# VGAX_board_rev_11_PAPER_VERSION_option_2.net
KiCad netlist of a schematic drawn in EAGLE
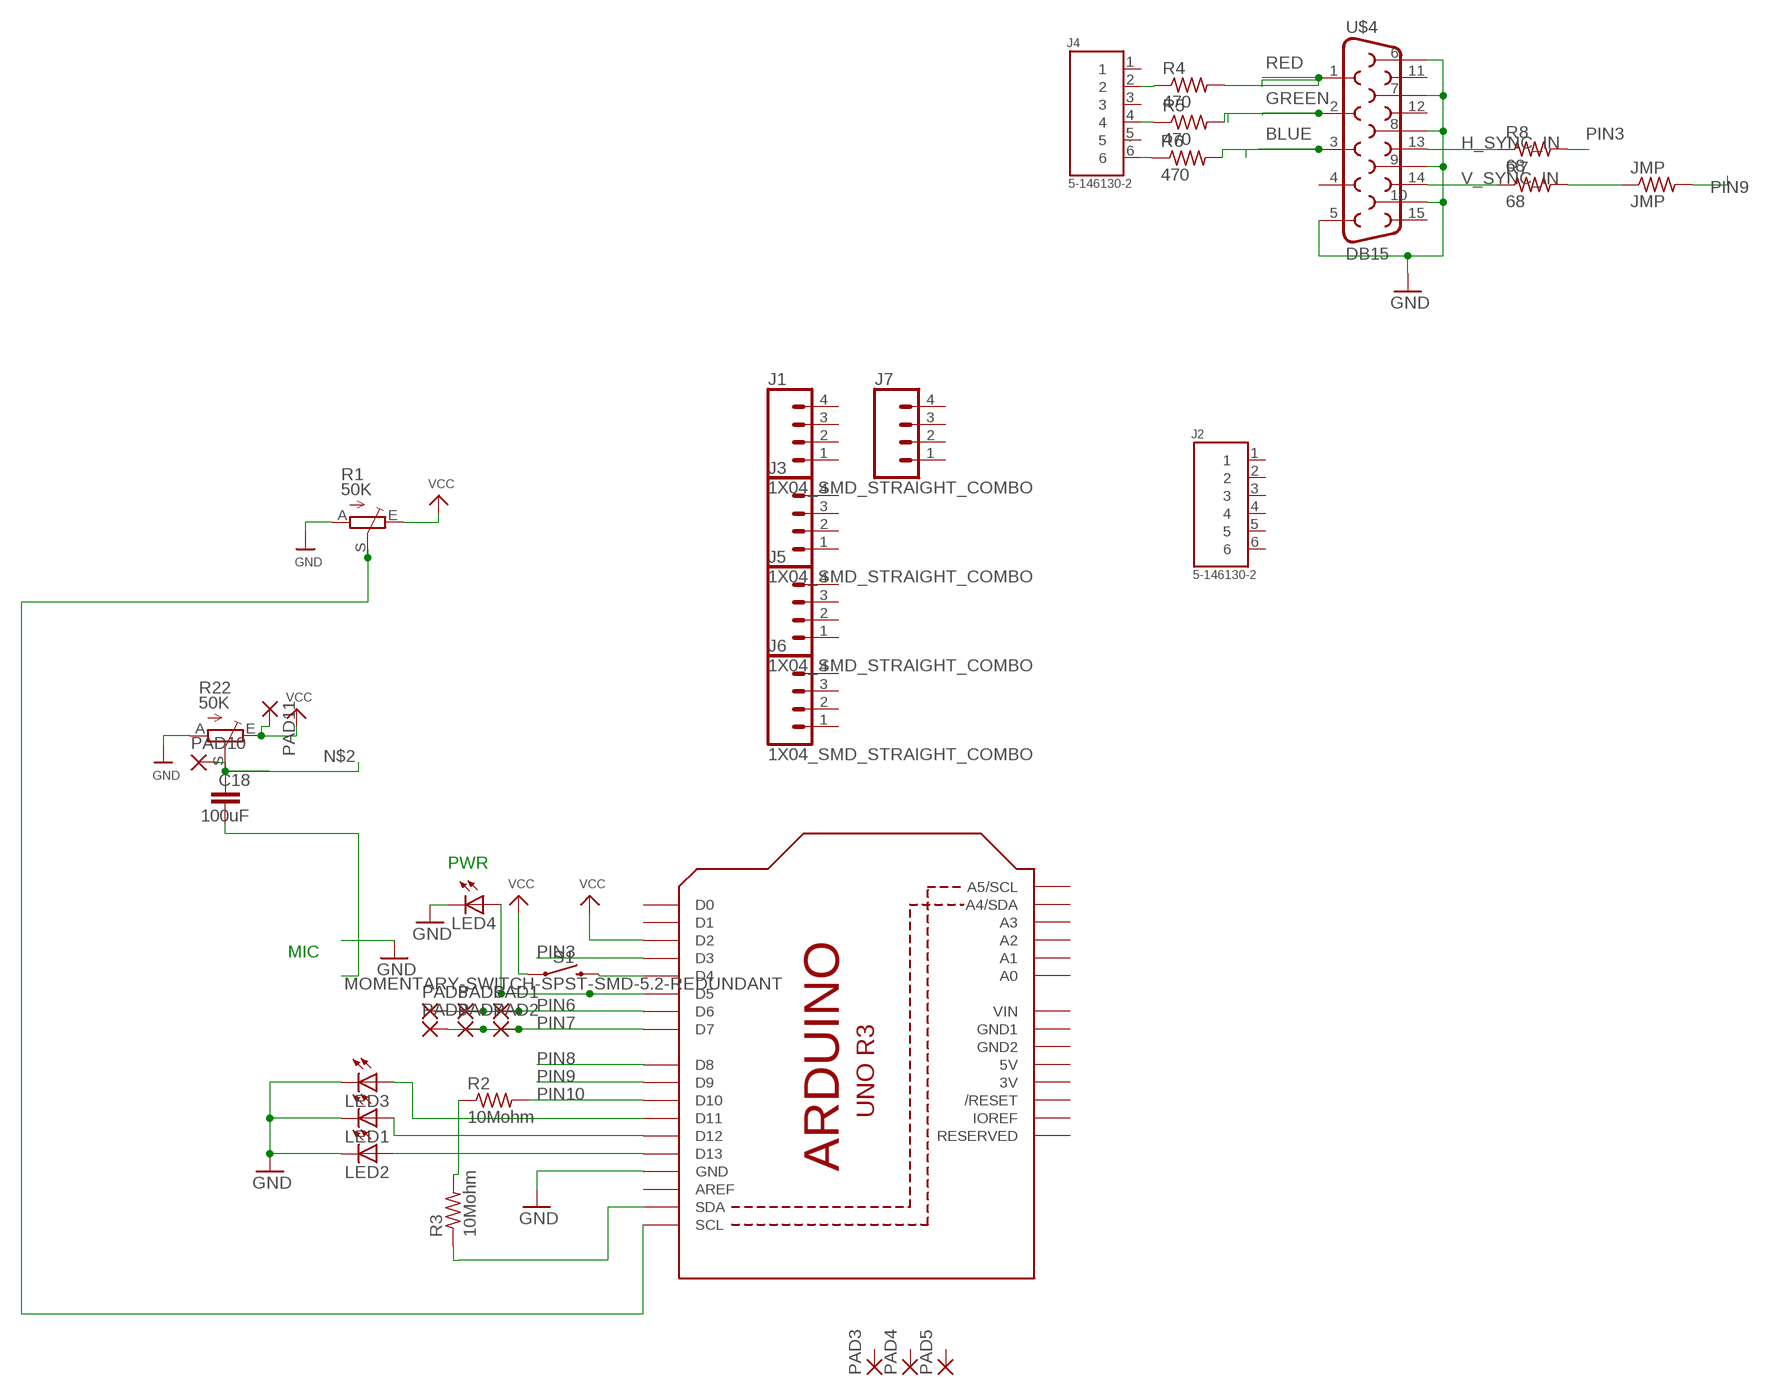
[diagram p0: schematic, sheet 1]

(export (version "E")
  (design (tool "Eeschema 10.0.6"))
  (components
    (comp (ref "C18")
      (value "100uF")
      (footprint "eagle-import:1206")
      (libsource (lib "eagle-import") (part "1.0UF-1206-50V-10%"))
    )
    (comp (ref "J1")
      (value "1X04_SMD_STRAIGHT_COMBO")
      (footprint "eagle-import:1X04_SMD_VERTICAL_COMBO")
      (libsource (lib "eagle-import") (part "CONN_04SMD_STRAIGHT_COMBO"))
    )
    (comp (ref "J2")
      (value "5-146130-2")
      (footprint "eagle-import:5-146130-2")
      (fields
        (field (name "DIGIKEY_PART_NUMBER") "5-146130-2-ND")
        (field (name "MANUFACTURER") "TE Connectivity AMP Connectors")
        (field (name "CREATED_BY") "PCBLayout.com")
      )
      (libsource (lib "eagle-import") (part "5-146130-2"))
    )
    (comp (ref "J3")
      (value "1X04_SMD_STRAIGHT_COMBO")
      (footprint "eagle-import:1X04_SMD_VERTICAL_COMBO")
      (libsource (lib "eagle-import") (part "CONN_04SMD_STRAIGHT_COMBO"))
    )
    (comp (ref "J4")
      (value "5-146130-2")
      (footprint "eagle-import:5-146130-2")
      (fields
        (field (name "DIGIKEY_PART_NUMBER") "5-146130-2-ND")
        (field (name "MANUFACTURER") "TE Connectivity AMP Connectors")
        (field (name "CREATED_BY") "PCBLayout.com")
      )
      (libsource (lib "eagle-import") (part "5-146130-2"))
    )
    (comp (ref "J5")
      (value "1X04_SMD_STRAIGHT_COMBO")
      (footprint "eagle-import:1X04_SMD_VERTICAL_COMBO")
      (libsource (lib "eagle-import") (part "CONN_04SMD_STRAIGHT_COMBO"))
    )
    (comp (ref "J6")
      (value "1X04_SMD_STRAIGHT_COMBO")
      (footprint "eagle-import:1X04_SMD_VERTICAL_COMBO")
      (libsource (lib "eagle-import") (part "CONN_04SMD_STRAIGHT_COMBO"))
    )
    (comp (ref "J7")
      (value "1X04_SMD_STRAIGHT_COMBO")
      (footprint "eagle-import:1X04_SMD_VERTICAL_COMBO")
      (libsource (lib "eagle-import") (part "CONN_04SMD_STRAIGHT_COMBO"))
    )
    (comp (ref "JMP")
      (value "JMP")
      (footprint "eagle-import:M1206")
      (libsource (lib "eagle-import") (part "R-US_M1206"))
    )
    (comp (ref "LED1")
      (value "LEDCHIPLED_1206")
      (footprint "eagle-import:CHIPLED_1206")
      (libsource (lib "eagle-import") (part "LEDCHIPLED_1206"))
    )
    (comp (ref "LED2")
      (value "LEDCHIPLED_1206")
      (footprint "eagle-import:CHIPLED_1206")
      (libsource (lib "eagle-import") (part "LEDCHIPLED_1206"))
    )
    (comp (ref "LED3")
      (value "LEDCHIPLED_1206")
      (footprint "eagle-import:CHIPLED_1206")
      (libsource (lib "eagle-import") (part "LEDCHIPLED_1206"))
    )
    (comp (ref "LED4")
      (value "LEDCHIPLED_1206")
      (footprint "eagle-import:CHIPLED_1206")
      (libsource (lib "eagle-import") (part "LEDCHIPLED_1206"))
    )
    (comp (ref "PAD1")
      (value "SMD2")
      (footprint "eagle-import:SMD1,27-2,54")
      (libsource (lib "eagle-import") (part "SMD2"))
    )
    (comp (ref "PAD2")
      (value "SMD2")
      (footprint "eagle-import:SMD1,27-2,54")
      (libsource (lib "eagle-import") (part "SMD2"))
    )
    (comp (ref "PAD3")
      (value "SMD2")
      (footprint "eagle-import:SMD1,27-2,54")
      (libsource (lib "eagle-import") (part "SMD2"))
    )
    (comp (ref "PAD4")
      (value "SMD2")
      (footprint "eagle-import:SMD1,27-2,54")
      (libsource (lib "eagle-import") (part "SMD2"))
    )
    (comp (ref "PAD5")
      (value "SMD2")
      (footprint "eagle-import:SMD1,27-2,54")
      (libsource (lib "eagle-import") (part "SMD2"))
    )
    (comp (ref "PAD6")
      (value "SMD2")
      (footprint "eagle-import:SMD1,27-2,54")
      (libsource (lib "eagle-import") (part "SMD2"))
    )
    (comp (ref "PAD7")
      (value "SMD2")
      (footprint "eagle-import:SMD1,27-2,54")
      (libsource (lib "eagle-import") (part "SMD2"))
    )
    (comp (ref "PAD8")
      (value "SMD2")
      (footprint "eagle-import:SMD1,27-2,54")
      (libsource (lib "eagle-import") (part "SMD2"))
    )
    (comp (ref "PAD9")
      (value "SMD2")
      (footprint "eagle-import:SMD1,27-2,54")
      (libsource (lib "eagle-import") (part "SMD2"))
    )
    (comp (ref "PAD10")
      (value "SMD2")
      (footprint "eagle-import:SMD1,27-2,54")
      (libsource (lib "eagle-import") (part "SMD2"))
    )
    (comp (ref "PAD11")
      (value "SMD2")
      (footprint "eagle-import:SMD1,27-2,54")
      (libsource (lib "eagle-import") (part "SMD2"))
    )
    (comp (ref "R1")
      (value "50K")
      (footprint "eagle-import:CA9V")
      (libsource (lib "eagle-import") (part "TRIM_EU-CA9V"))
    )
    (comp (ref "R2")
      (value "10Mohm")
      (footprint "eagle-import:M1206")
      (libsource (lib "eagle-import") (part "R-US_M1206"))
    )
    (comp (ref "R3")
      (value "10Mohm")
      (footprint "eagle-import:M1206")
      (libsource (lib "eagle-import") (part "R-US_M1206"))
    )
    (comp (ref "R4")
      (value "470")
      (footprint "eagle-import:M1206")
      (libsource (lib "eagle-import") (part "R-US_M1206"))
    )
    (comp (ref "R5")
      (value "470")
      (footprint "eagle-import:M1206")
      (libsource (lib "eagle-import") (part "R-US_M1206"))
    )
    (comp (ref "R6")
      (value "470")
      (footprint "eagle-import:M1206")
      (libsource (lib "eagle-import") (part "R-US_M1206"))
    )
    (comp (ref "R7")
      (value "68")
      (footprint "eagle-import:M1206")
      (libsource (lib "eagle-import") (part "R-US_M1206"))
    )
    (comp (ref "R8")
      (value "68")
      (footprint "eagle-import:M1206")
      (libsource (lib "eagle-import") (part "R-US_M1206"))
    )
    (comp (ref "R22")
      (value "50K")
      (footprint "eagle-import:CA9V")
      (libsource (lib "eagle-import") (part "TRIM_EU-CA9V"))
    )
    (comp (ref "S1")
      (value "MOMENTARY-SWITCH-SPST-SMD-5.2-REDUNDANT")
      (footprint "eagle-import:TACTILE_SWITCH_SMD_5.2MM")
      (libsource (lib "eagle-import") (part "MOMENTARY-SWITCH-SPST-SMD-5.2-REDUNDANT"))
    )
    (comp (ref "U$4")
      (value "DB15")
      (footprint "eagle-import:DB15")
      (libsource (lib "eagle-import") (part "DB15"))
    )
    (comp (ref "U1")
      (value "ARDUINOR3-BPLACE")
      (footprint "eagle-import:ARDUINOR3-BPLACE")
      (libsource (lib "eagle-import") (part "ARDUINOR3-BPLACE"))
    )
  )
  (nets
    (net (code "1") (name "/3V") (class "Default")
      (node (ref "U1") (pin "3V") (pinfunction "3V_3V") (pintype "power_in"))
    )
    (net (code "2") (name "/5V") (class "Default")
      (node (ref "U1") (pin "5V") (pinfunction "5V_5V") (pintype "power_in"))
    )
    (net (code "3") (name "/BLUE") (class "Default")
      (node (ref "R6") (pin "2") (pinfunction "2_2") (pintype "passive"))
      (node (ref "U$4") (pin "3") (pinfunction "3_3") (pintype "passive"))
    )
    (net (code "4") (name "/GND1") (class "Default")
      (node (ref "U1") (pin "GND1") (pinfunction "GND1_GND1") (pintype "power_in"))
    )
    (net (code "5") (name "/GND2") (class "Default")
      (node (ref "U1") (pin "GND2") (pinfunction "GND2_GND2") (pintype "power_in"))
    )
    (net (code "6") (name "/GREEN") (class "Default")
      (node (ref "R5") (pin "2") (pinfunction "2_2") (pintype "passive"))
      (node (ref "U$4") (pin "2") (pinfunction "2_2") (pintype "passive"))
    )
    (net (code "7") (name "/H_SYNC_IN") (class "Default")
      (node (ref "R8") (pin "1") (pinfunction "1_1") (pintype "passive"))
      (node (ref "U$4") (pin "13") (pinfunction "13_13") (pintype "passive"))
    )
    (net (code "8") (name "/N$2") (class "Default")
      (node (ref "C18") (pin "1") (pinfunction "1_1") (pintype "passive"))
      (node (ref "PAD10") (pin "1") (pinfunction "P_1") (pintype "passive"))
      (node (ref "R22") (pin "S") (pinfunction "S_S") (pintype "passive"))
    )
    (net (code "9") (name "/PIN3") (class "Default")
      (node (ref "R8") (pin "2") (pinfunction "2_2") (pintype "passive"))
      (node (ref "U1") (pin "D3") (pinfunction "D3_D3") (pintype "bidirectional"))
    )
    (net (code "10") (name "/PIN6") (class "Default")
      (node (ref "PAD1") (pin "1") (pinfunction "P_1") (pintype "passive"))
      (node (ref "PAD6") (pin "1") (pinfunction "P_1") (pintype "passive"))
      (node (ref "PAD8") (pin "1") (pinfunction "P_1") (pintype "passive"))
      (node (ref "U1") (pin "D6") (pinfunction "D6_D6") (pintype "bidirectional"))
    )
    (net (code "11") (name "/PIN7") (class "Default")
      (node (ref "PAD2") (pin "1") (pinfunction "P_1") (pintype "passive"))
      (node (ref "PAD7") (pin "1") (pinfunction "P_1") (pintype "passive"))
      (node (ref "PAD9") (pin "1") (pinfunction "P_1") (pintype "passive"))
      (node (ref "U1") (pin "D7") (pinfunction "D7_D7") (pintype "bidirectional"))
    )
    (net (code "12") (name "/PIN8") (class "Default")
      (node (ref "R3") (pin "1") (pinfunction "1_1") (pintype "passive"))
      (node (ref "U1") (pin "D8") (pinfunction "D8_D8") (pintype "bidirectional"))
      (node (ref "U1") (pin "SDA") (pinfunction "SDA_SDA") (pintype "bidirectional"))
    )
    (net (code "13") (name "/PIN9") (class "Default")
      (node (ref "JMP") (pin "2") (pinfunction "2_2") (pintype "passive"))
      (node (ref "U1") (pin "D9") (pinfunction "D9_D9") (pintype "bidirectional"))
    )
    (net (code "14") (name "/PIN10") (class "Default")
      (node (ref "R2") (pin "2") (pinfunction "2_2") (pintype "passive"))
      (node (ref "U1") (pin "D10") (pinfunction "D10_D10") (pintype "bidirectional"))
    )
    (net (code "15") (name "/RED") (class "Default")
      (node (ref "R4") (pin "2") (pinfunction "2_2") (pintype "passive"))
      (node (ref "U$4") (pin "1") (pinfunction "1_1") (pintype "passive"))
    )
    (net (code "16") (name "/VIN") (class "Default")
      (node (ref "U1") (pin "VIN") (pinfunction "VIN_VIN") (pintype "power_in"))
    )
    (net (code "17") (name "/V_SYNC_IN") (class "Default")
      (node (ref "R7") (pin "1") (pinfunction "1_1") (pintype "passive"))
      (node (ref "U$4") (pin "14") (pinfunction "14_14") (pintype "passive"))
    )
    (net (code "18") (name "GND") (class "Default")
      (node (ref "LED1") (pin "C") (pinfunction "C_C") (pintype "passive"))
      (node (ref "LED2") (pin "C") (pinfunction "C_C") (pintype "passive"))
      (node (ref "LED3") (pin "C") (pinfunction "C_C") (pintype "passive"))
      (node (ref "LED4") (pin "C") (pinfunction "C_C") (pintype "passive"))
      (node (ref "R1") (pin "A") (pinfunction "A_A") (pintype "passive"))
      (node (ref "R22") (pin "A") (pinfunction "A_A") (pintype "passive"))
      (node (ref "U$4") (pin "10") (pinfunction "10_10") (pintype "passive"))
      (node (ref "U$4") (pin "5") (pinfunction "5_5") (pintype "passive"))
      (node (ref "U$4") (pin "6") (pinfunction "6_6") (pintype "passive"))
      (node (ref "U$4") (pin "7") (pinfunction "7_7") (pintype "passive"))
      (node (ref "U$4") (pin "8") (pinfunction "8_8") (pintype "passive"))
      (node (ref "U$4") (pin "9") (pinfunction "9_9") (pintype "passive"))
      (node (ref "U1") (pin "GND") (pinfunction "GND_GND") (pintype "power_in"))
    )
    (net (code "19") (name "Net-(J4-Pad2)") (class "Default")
      (node (ref "J4") (pin "2") (pinfunction "2_2") (pintype "passive"))
      (node (ref "R4") (pin "1") (pinfunction "1_1") (pintype "passive"))
    )
    (net (code "20") (name "Net-(J4-Pad4)") (class "Default")
      (node (ref "J4") (pin "4") (pinfunction "4_4") (pintype "passive"))
      (node (ref "R5") (pin "1") (pinfunction "1_1") (pintype "passive"))
    )
    (net (code "21") (name "Net-(J4-Pad6)") (class "Default")
      (node (ref "J4") (pin "6") (pinfunction "6_6") (pintype "passive"))
      (node (ref "R6") (pin "1") (pinfunction "1_1") (pintype "passive"))
    )
    (net (code "22") (name "Net-(JMP-Pad1)") (class "Default")
      (node (ref "JMP") (pin "1") (pinfunction "1_1") (pintype "passive"))
      (node (ref "R7") (pin "2") (pinfunction "2_2") (pintype "passive"))
    )
    (net (code "23") (name "Net-(LED1-PadA)") (class "Default")
      (node (ref "LED1") (pin "A") (pinfunction "A_A") (pintype "passive"))
      (node (ref "U1") (pin "D12") (pinfunction "D12_D12") (pintype "bidirectional"))
    )
    (net (code "24") (name "Net-(LED2-PadA)") (class "Default")
      (node (ref "LED2") (pin "A") (pinfunction "A_A") (pintype "passive"))
      (node (ref "U1") (pin "D13") (pinfunction "D13_D13") (pintype "bidirectional"))
    )
    (net (code "25") (name "Net-(LED3-PadA)") (class "Default")
      (node (ref "LED3") (pin "A") (pinfunction "A_A") (pintype "passive"))
      (node (ref "U1") (pin "D11") (pinfunction "D11_D11") (pintype "bidirectional"))
    )
    (net (code "26") (name "Net-(LED4-PadA)") (class "Default")
      (node (ref "LED4") (pin "A") (pinfunction "A_A") (pintype "passive"))
      (node (ref "U1") (pin "D5") (pinfunction "D5_D5") (pintype "bidirectional"))
    )
    (net (code "27") (name "Net-(R1-PadS)") (class "Default")
      (node (ref "R1") (pin "S") (pinfunction "S_S") (pintype "passive"))
      (node (ref "U1") (pin "SCL") (pinfunction "SCL_SCL") (pintype "bidirectional"))
    )
    (net (code "28") (name "Net-(R2-Pad1)") (class "Default")
      (node (ref "R2") (pin "1") (pinfunction "1_1") (pintype "passive"))
      (node (ref "R3") (pin "2") (pinfunction "2_2") (pintype "passive"))
    )
    (net (code "29") (name "Net-(S1-2-Pad3)") (class "Default")
      (node (ref "S1") (pin "3") (pinfunction "2_3") (pintype "passive"))
      (node (ref "S1") (pin "4") (pinfunction "2_4") (pintype "passive"))
      (node (ref "U1") (pin "D4") (pinfunction "D4_D4") (pintype "bidirectional"))
    )
    (net (code "30") (name "VCC") (class "Default")
      (node (ref "PAD11") (pin "1") (pinfunction "P_1") (pintype "passive"))
      (node (ref "R1") (pin "E") (pinfunction "E_E") (pintype "passive"))
      (node (ref "R22") (pin "E") (pinfunction "E_E") (pintype "passive"))
      (node (ref "S1") (pin "1") (pinfunction "1_1") (pintype "passive"))
      (node (ref "S1") (pin "2") (pinfunction "1_2") (pintype "passive"))
      (node (ref "U1") (pin "D2") (pinfunction "D2_D2") (pintype "bidirectional"))
    )
    (net (code "31") (name "unconnected-(C18-Pad2)") (class "Default")
      (node (ref "C18") (pin "2") (pinfunction "2_2") (pintype "passive"))
    )
    (net (code "32") (name "unconnected-(J1-Pad1)") (class "Default")
      (node (ref "J1") (pin "1") (pinfunction "1_1") (pintype "passive"))
    )
    (net (code "33") (name "unconnected-(J1-Pad2)") (class "Default")
      (node (ref "J1") (pin "2") (pinfunction "2_2") (pintype "passive"))
    )
    (net (code "34") (name "unconnected-(J1-Pad3)") (class "Default")
      (node (ref "J1") (pin "3") (pinfunction "3_3") (pintype "passive"))
    )
    (net (code "35") (name "unconnected-(J1-Pad4)") (class "Default")
      (node (ref "J1") (pin "4") (pinfunction "4_4") (pintype "passive"))
    )
    (net (code "36") (name "unconnected-(J2-Pad1)") (class "Default")
      (node (ref "J2") (pin "1") (pinfunction "1_1") (pintype "passive"))
    )
    (net (code "37") (name "unconnected-(J2-Pad2)") (class "Default")
      (node (ref "J2") (pin "2") (pinfunction "2_2") (pintype "passive"))
    )
    (net (code "38") (name "unconnected-(J2-Pad3)") (class "Default")
      (node (ref "J2") (pin "3") (pinfunction "3_3") (pintype "passive"))
    )
    (net (code "39") (name "unconnected-(J2-Pad4)") (class "Default")
      (node (ref "J2") (pin "4") (pinfunction "4_4") (pintype "passive"))
    )
    (net (code "40") (name "unconnected-(J2-Pad5)") (class "Default")
      (node (ref "J2") (pin "5") (pinfunction "5_5") (pintype "passive"))
    )
    (net (code "41") (name "unconnected-(J2-Pad6)") (class "Default")
      (node (ref "J2") (pin "6") (pinfunction "6_6") (pintype "passive"))
    )
    (net (code "42") (name "unconnected-(J3-Pad1)") (class "Default")
      (node (ref "J3") (pin "1") (pinfunction "1_1") (pintype "passive"))
    )
    (net (code "43") (name "unconnected-(J3-Pad2)") (class "Default")
      (node (ref "J3") (pin "2") (pinfunction "2_2") (pintype "passive"))
    )
    (net (code "44") (name "unconnected-(J3-Pad3)") (class "Default")
      (node (ref "J3") (pin "3") (pinfunction "3_3") (pintype "passive"))
    )
    (net (code "45") (name "unconnected-(J3-Pad4)") (class "Default")
      (node (ref "J3") (pin "4") (pinfunction "4_4") (pintype "passive"))
    )
    (net (code "46") (name "unconnected-(J4-Pad1)") (class "Default")
      (node (ref "J4") (pin "1") (pinfunction "1_1") (pintype "passive"))
    )
    (net (code "47") (name "unconnected-(J4-Pad3)") (class "Default")
      (node (ref "J4") (pin "3") (pinfunction "3_3") (pintype "passive"))
    )
    (net (code "48") (name "unconnected-(J4-Pad5)") (class "Default")
      (node (ref "J4") (pin "5") (pinfunction "5_5") (pintype "passive"))
    )
    (net (code "49") (name "unconnected-(J5-Pad1)") (class "Default")
      (node (ref "J5") (pin "1") (pinfunction "1_1") (pintype "passive"))
    )
    (net (code "50") (name "unconnected-(J5-Pad2)") (class "Default")
      (node (ref "J5") (pin "2") (pinfunction "2_2") (pintype "passive"))
    )
    (net (code "51") (name "unconnected-(J5-Pad3)") (class "Default")
      (node (ref "J5") (pin "3") (pinfunction "3_3") (pintype "passive"))
    )
    (net (code "52") (name "unconnected-(J5-Pad4)") (class "Default")
      (node (ref "J5") (pin "4") (pinfunction "4_4") (pintype "passive"))
    )
    (net (code "53") (name "unconnected-(J6-Pad1)") (class "Default")
      (node (ref "J6") (pin "1") (pinfunction "1_1") (pintype "passive"))
    )
    (net (code "54") (name "unconnected-(J6-Pad2)") (class "Default")
      (node (ref "J6") (pin "2") (pinfunction "2_2") (pintype "passive"))
    )
    (net (code "55") (name "unconnected-(J6-Pad3)") (class "Default")
      (node (ref "J6") (pin "3") (pinfunction "3_3") (pintype "passive"))
    )
    (net (code "56") (name "unconnected-(J6-Pad4)") (class "Default")
      (node (ref "J6") (pin "4") (pinfunction "4_4") (pintype "passive"))
    )
    (net (code "57") (name "unconnected-(J7-Pad1)") (class "Default")
      (node (ref "J7") (pin "1") (pinfunction "1_1") (pintype "passive"))
    )
    (net (code "58") (name "unconnected-(J7-Pad2)") (class "Default")
      (node (ref "J7") (pin "2") (pinfunction "2_2") (pintype "passive"))
    )
    (net (code "59") (name "unconnected-(J7-Pad3)") (class "Default")
      (node (ref "J7") (pin "3") (pinfunction "3_3") (pintype "passive"))
    )
    (net (code "60") (name "unconnected-(J7-Pad4)") (class "Default")
      (node (ref "J7") (pin "4") (pinfunction "4_4") (pintype "passive"))
    )
    (net (code "61") (name "unconnected-(PAD3-P-Pad1)") (class "Default")
      (node (ref "PAD3") (pin "1") (pinfunction "P_1") (pintype "passive"))
    )
    (net (code "62") (name "unconnected-(PAD4-P-Pad1)") (class "Default")
      (node (ref "PAD4") (pin "1") (pinfunction "P_1") (pintype "passive"))
    )
    (net (code "63") (name "unconnected-(PAD5-P-Pad1)") (class "Default")
      (node (ref "PAD5") (pin "1") (pinfunction "P_1") (pintype "passive"))
    )
    (net (code "64") (name "unconnected-(U$4-Pad4)") (class "Default")
      (node (ref "U$4") (pin "4") (pinfunction "4_4") (pintype "passive"))
    )
    (net (code "65") (name "unconnected-(U$4-Pad11)") (class "Default")
      (node (ref "U$4") (pin "11") (pinfunction "11_11") (pintype "passive"))
    )
    (net (code "66") (name "unconnected-(U$4-Pad12)") (class "Default")
      (node (ref "U$4") (pin "12") (pinfunction "12_12") (pintype "passive"))
    )
    (net (code "67") (name "unconnected-(U$4-Pad15)") (class "Default")
      (node (ref "U$4") (pin "15") (pinfunction "15_15") (pintype "passive"))
    )
    (net (code "68") (name "unconnected-(U1-A4{slash}SDA-PadA4)") (class "Default")
      (node (ref "U1") (pin "A4") (pinfunction "A4/SDA_A4") (pintype "bidirectional"))
    )
    (net (code "69") (name "unconnected-(U1-A5{slash}SCL-PadA5)") (class "Default")
      (node (ref "U1") (pin "A5") (pinfunction "A5/SCL_A5") (pintype "bidirectional"))
    )
    (net (code "70") (name "unconnected-(U1-PadA0)") (class "Default")
      (node (ref "U1") (pin "A0") (pinfunction "A0_A0") (pintype "bidirectional"))
    )
    (net (code "71") (name "unconnected-(U1-PadA1)") (class "Default")
      (node (ref "U1") (pin "A1") (pinfunction "A1_A1") (pintype "bidirectional"))
    )
    (net (code "72") (name "unconnected-(U1-PadA2)") (class "Default")
      (node (ref "U1") (pin "A2") (pinfunction "A2_A2") (pintype "bidirectional"))
    )
    (net (code "73") (name "unconnected-(U1-PadA3)") (class "Default")
      (node (ref "U1") (pin "A3") (pinfunction "A3_A3") (pintype "bidirectional"))
    )
    (net (code "74") (name "unconnected-(U1-PadAREF)") (class "Default")
      (node (ref "U1") (pin "AREF") (pinfunction "AREF_AREF") (pintype "bidirectional"))
    )
    (net (code "75") (name "unconnected-(U1-PadD0)") (class "Default")
      (node (ref "U1") (pin "D0") (pinfunction "D0_D0") (pintype "bidirectional"))
    )
    (net (code "76") (name "unconnected-(U1-PadD1)") (class "Default")
      (node (ref "U1") (pin "D1") (pinfunction "D1_D1") (pintype "bidirectional"))
    )
    (net (code "77") (name "unconnected-(U1-PadIOREF)") (class "Default")
      (node (ref "U1") (pin "IOREF") (pinfunction "IOREF_IOREF") (pintype "output"))
    )
    (net (code "78") (name "unconnected-(U1-PadRESERVED)") (class "Default")
      (node (ref "U1") (pin "RESERVED") (pinfunction "RESERVED_RESERVED") (pintype "no_connect"))
    )
    (net (code "79") (name "unconnected-(U1-{slash}RESET-PadRESET)") (class "Default")
      (node (ref "U1") (pin "RESET") (pinfunction "/RESET_RESET") (pintype "bidirectional"))
    )
  )
)
